# FlipDotModule.net
KiCad netlist of a schematic drawn in EAGLE
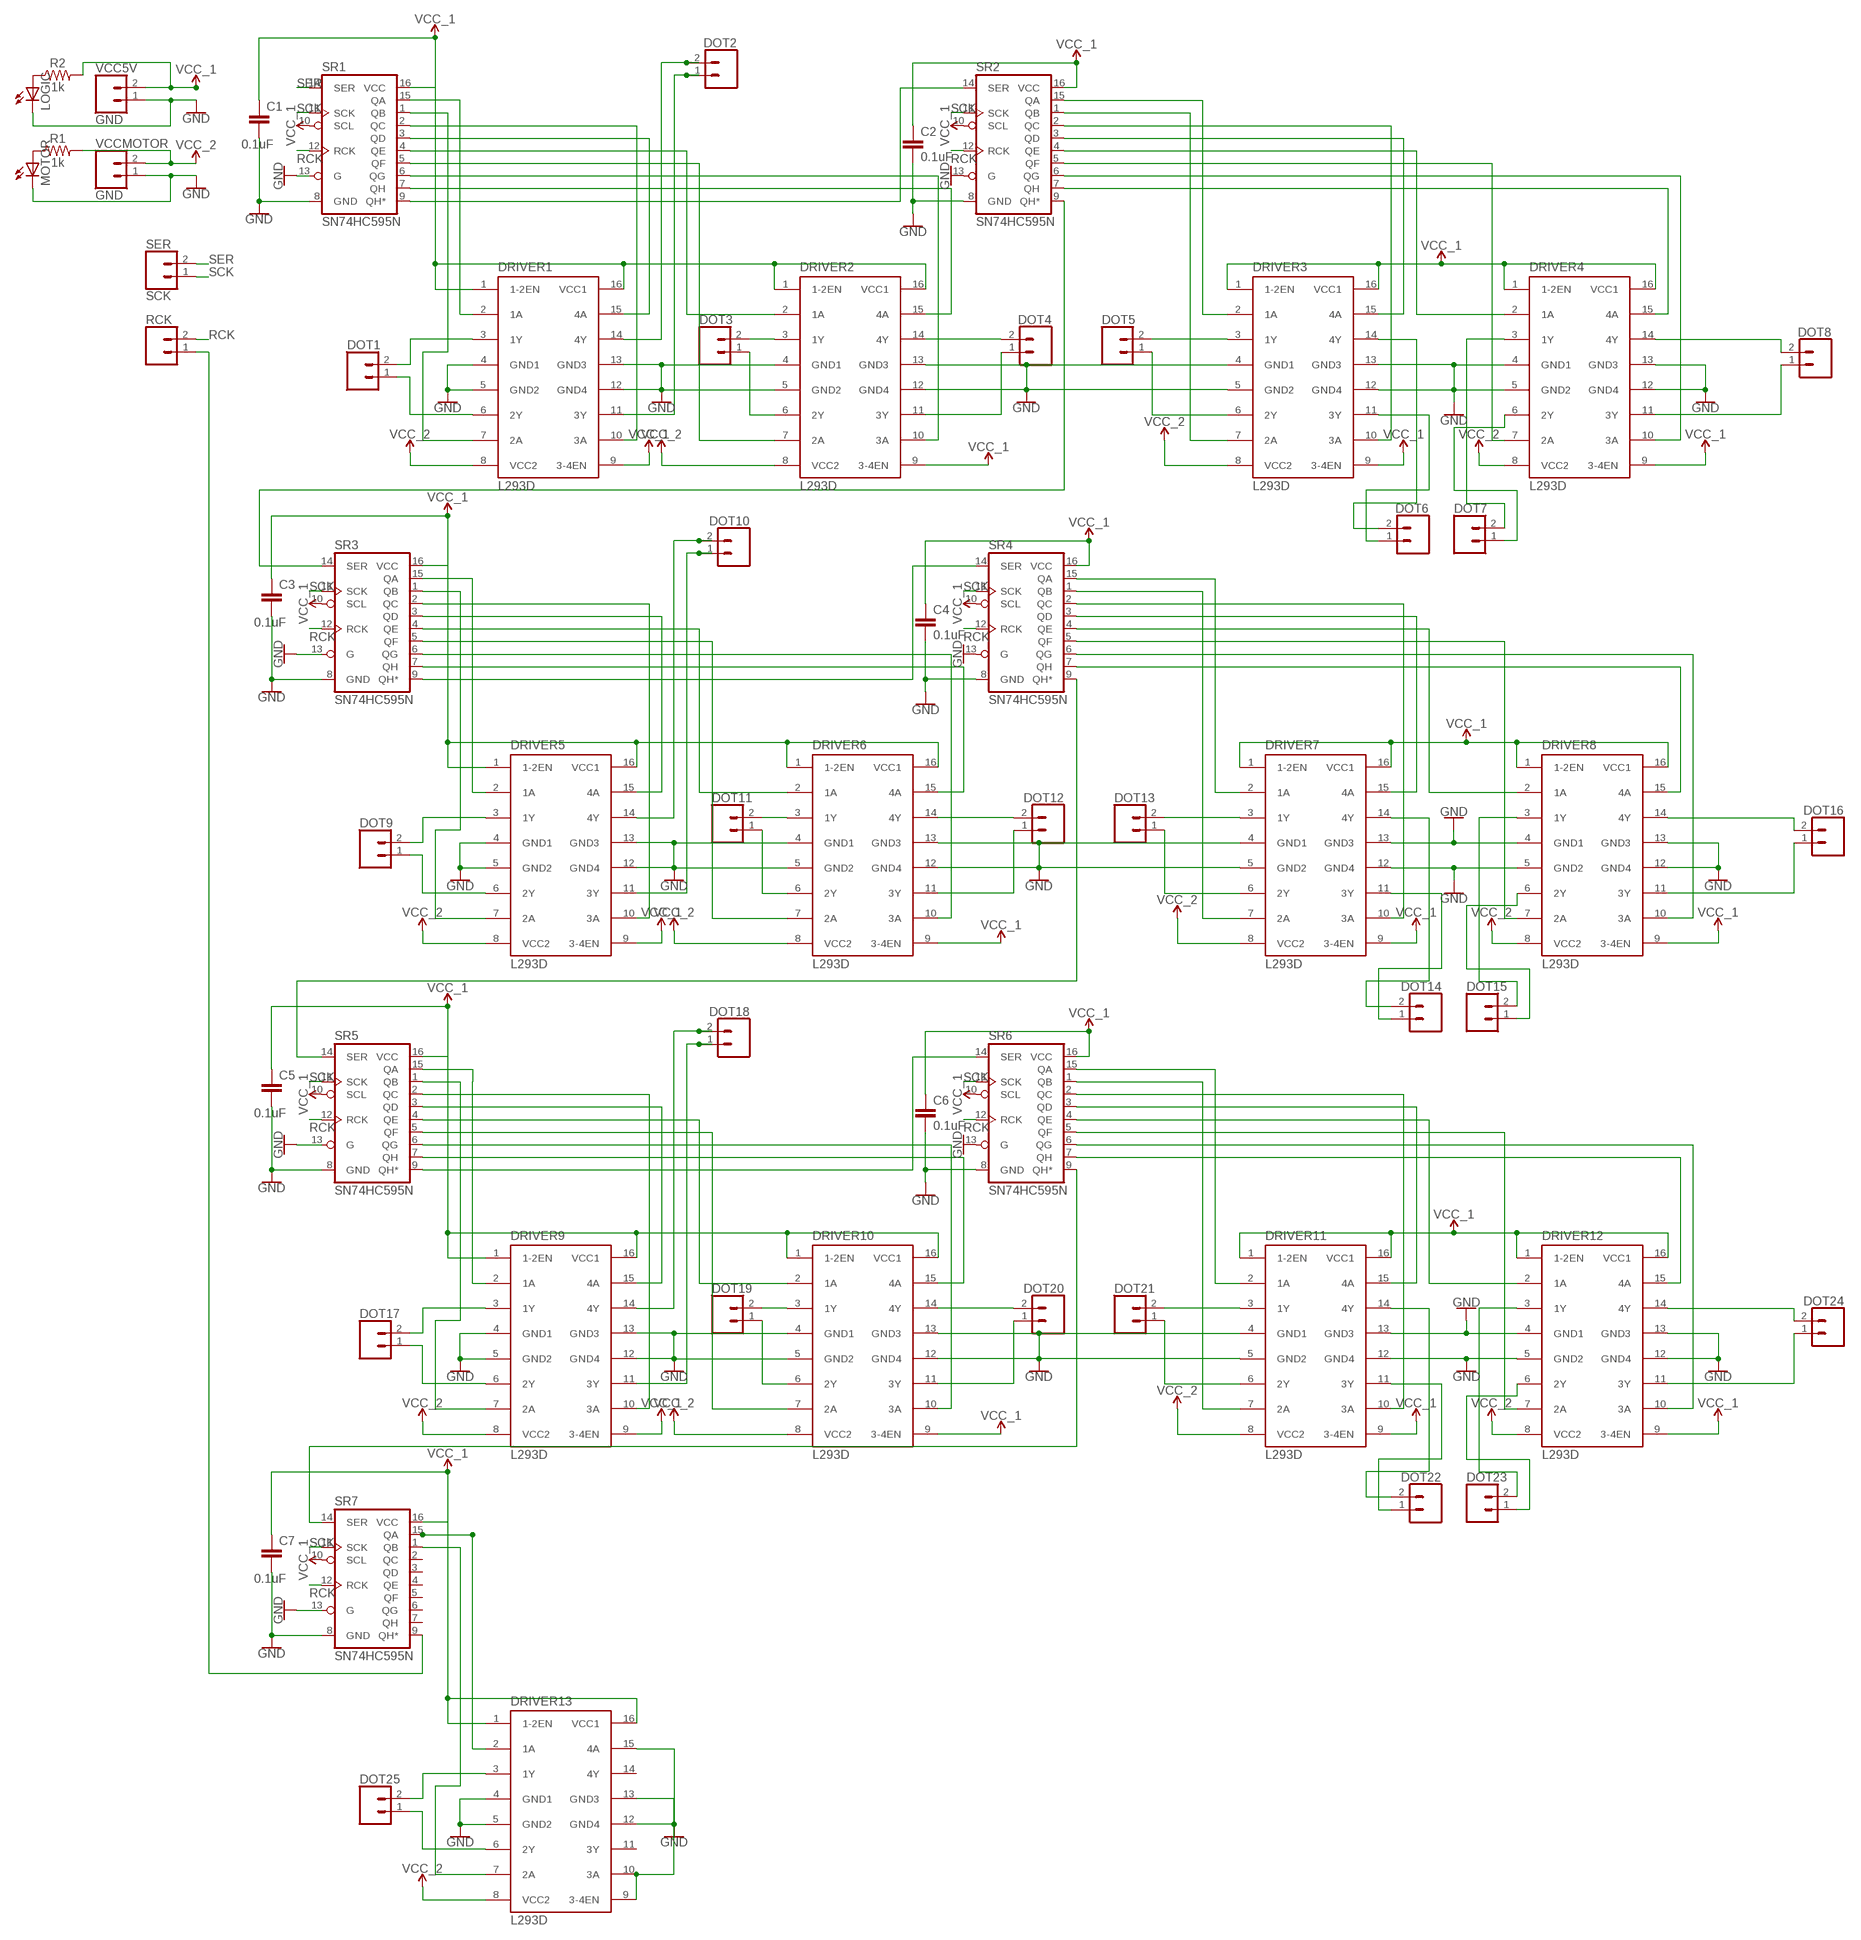
[diagram p0: schematic, sheet 1, part 1 of 2]
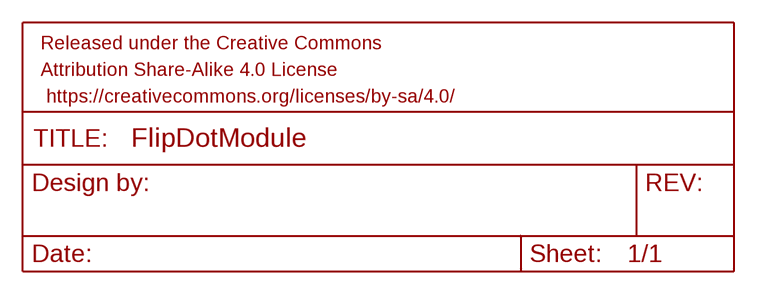
[diagram p1: schematic, sheet 1, part 2 of 2]

(export (version "E")
  (design (tool "Eeschema 10.0.6"))
  (components
    (comp (ref "C1")
      (value "0.1uF")
      (footprint "eagle-import:CAP-PTH-SMALL-KIT")
      (libsource (lib "eagle-import") (part "0.1UF-KIT-EZ-50V-20%"))
    )
    (comp (ref "C2")
      (value "0.1uF")
      (footprint "eagle-import:CAP-PTH-SMALL-KIT")
      (libsource (lib "eagle-import") (part "0.1UF-KIT-EZ-50V-20%"))
    )
    (comp (ref "C3")
      (value "0.1uF")
      (footprint "eagle-import:CAP-PTH-SMALL-KIT")
      (libsource (lib "eagle-import") (part "0.1UF-KIT-EZ-50V-20%"))
    )
    (comp (ref "C4")
      (value "0.1uF")
      (footprint "eagle-import:CAP-PTH-SMALL-KIT")
      (libsource (lib "eagle-import") (part "0.1UF-KIT-EZ-50V-20%"))
    )
    (comp (ref "C5")
      (value "0.1uF")
      (footprint "eagle-import:CAP-PTH-SMALL-KIT")
      (libsource (lib "eagle-import") (part "0.1UF-KIT-EZ-50V-20%"))
    )
    (comp (ref "C6")
      (value "0.1uF")
      (footprint "eagle-import:CAP-PTH-SMALL-KIT")
      (libsource (lib "eagle-import") (part "0.1UF-KIT-EZ-50V-20%"))
    )
    (comp (ref "C7")
      (value "0.1uF")
      (footprint "eagle-import:CAP-PTH-SMALL-KIT")
      (libsource (lib "eagle-import") (part "0.1UF-KIT-EZ-50V-20%"))
    )
    (comp (ref "DOT1")
      (value "CONN_025MM")
      (footprint "eagle-import:SCREWTERMINAL-5MM-2")
      (libsource (lib "eagle-import") (part "CONN_025MM"))
    )
    (comp (ref "DOT2")
      (value "CONN_025MM")
      (footprint "eagle-import:SCREWTERMINAL-5MM-2")
      (libsource (lib "eagle-import") (part "CONN_025MM"))
    )
    (comp (ref "DOT3")
      (value "CONN_025MM")
      (footprint "eagle-import:SCREWTERMINAL-5MM-2")
      (libsource (lib "eagle-import") (part "CONN_025MM"))
    )
    (comp (ref "DOT4")
      (value "CONN_025MM")
      (footprint "eagle-import:SCREWTERMINAL-5MM-2")
      (libsource (lib "eagle-import") (part "CONN_025MM"))
    )
    (comp (ref "DOT5")
      (value "CONN_025MM")
      (footprint "eagle-import:SCREWTERMINAL-5MM-2")
      (libsource (lib "eagle-import") (part "CONN_025MM"))
    )
    (comp (ref "DOT6")
      (value "CONN_025MM")
      (footprint "eagle-import:SCREWTERMINAL-5MM-2")
      (libsource (lib "eagle-import") (part "CONN_025MM"))
    )
    (comp (ref "DOT7")
      (value "CONN_025MM")
      (footprint "eagle-import:SCREWTERMINAL-5MM-2")
      (libsource (lib "eagle-import") (part "CONN_025MM"))
    )
    (comp (ref "DOT8")
      (value "CONN_025MM")
      (footprint "eagle-import:SCREWTERMINAL-5MM-2")
      (libsource (lib "eagle-import") (part "CONN_025MM"))
    )
    (comp (ref "DOT9")
      (value "CONN_025MM")
      (footprint "eagle-import:SCREWTERMINAL-5MM-2")
      (libsource (lib "eagle-import") (part "CONN_025MM"))
    )
    (comp (ref "DOT10")
      (value "CONN_025MM")
      (footprint "eagle-import:SCREWTERMINAL-5MM-2")
      (libsource (lib "eagle-import") (part "CONN_025MM"))
    )
    (comp (ref "DOT11")
      (value "CONN_025MM")
      (footprint "eagle-import:SCREWTERMINAL-5MM-2")
      (libsource (lib "eagle-import") (part "CONN_025MM"))
    )
    (comp (ref "DOT12")
      (value "CONN_025MM")
      (footprint "eagle-import:SCREWTERMINAL-5MM-2")
      (libsource (lib "eagle-import") (part "CONN_025MM"))
    )
    (comp (ref "DOT13")
      (value "CONN_025MM")
      (footprint "eagle-import:SCREWTERMINAL-5MM-2")
      (libsource (lib "eagle-import") (part "CONN_025MM"))
    )
    (comp (ref "DOT14")
      (value "CONN_025MM")
      (footprint "eagle-import:SCREWTERMINAL-5MM-2")
      (libsource (lib "eagle-import") (part "CONN_025MM"))
    )
    (comp (ref "DOT15")
      (value "CONN_025MM")
      (footprint "eagle-import:SCREWTERMINAL-5MM-2")
      (libsource (lib "eagle-import") (part "CONN_025MM"))
    )
    (comp (ref "DOT16")
      (value "CONN_025MM")
      (footprint "eagle-import:SCREWTERMINAL-5MM-2")
      (libsource (lib "eagle-import") (part "CONN_025MM"))
    )
    (comp (ref "DOT17")
      (value "CONN_025MM")
      (footprint "eagle-import:SCREWTERMINAL-5MM-2")
      (libsource (lib "eagle-import") (part "CONN_025MM"))
    )
    (comp (ref "DOT18")
      (value "CONN_025MM")
      (footprint "eagle-import:SCREWTERMINAL-5MM-2")
      (libsource (lib "eagle-import") (part "CONN_025MM"))
    )
    (comp (ref "DOT19")
      (value "CONN_025MM")
      (footprint "eagle-import:SCREWTERMINAL-5MM-2")
      (libsource (lib "eagle-import") (part "CONN_025MM"))
    )
    (comp (ref "DOT20")
      (value "CONN_025MM")
      (footprint "eagle-import:SCREWTERMINAL-5MM-2")
      (libsource (lib "eagle-import") (part "CONN_025MM"))
    )
    (comp (ref "DOT21")
      (value "CONN_025MM")
      (footprint "eagle-import:SCREWTERMINAL-5MM-2")
      (libsource (lib "eagle-import") (part "CONN_025MM"))
    )
    (comp (ref "DOT22")
      (value "CONN_025MM")
      (footprint "eagle-import:SCREWTERMINAL-5MM-2")
      (libsource (lib "eagle-import") (part "CONN_025MM"))
    )
    (comp (ref "DOT23")
      (value "CONN_025MM")
      (footprint "eagle-import:SCREWTERMINAL-5MM-2")
      (libsource (lib "eagle-import") (part "CONN_025MM"))
    )
    (comp (ref "DOT24")
      (value "CONN_025MM")
      (footprint "eagle-import:SCREWTERMINAL-5MM-2")
      (libsource (lib "eagle-import") (part "CONN_025MM"))
    )
    (comp (ref "DOT25")
      (value "CONN_025MM")
      (footprint "eagle-import:SCREWTERMINAL-5MM-2")
      (libsource (lib "eagle-import") (part "CONN_025MM"))
    )
    (comp (ref "DRIVER1")
      (value "L293D")
      (footprint "eagle-import:DIL16")
      (libsource (lib "eagle-import") (part "L293D"))
    )
    (comp (ref "DRIVER2")
      (value "L293D")
      (footprint "eagle-import:DIL16")
      (libsource (lib "eagle-import") (part "L293D"))
    )
    (comp (ref "DRIVER3")
      (value "L293D")
      (footprint "eagle-import:DIL16")
      (libsource (lib "eagle-import") (part "L293D"))
    )
    (comp (ref "DRIVER4")
      (value "L293D")
      (footprint "eagle-import:DIL16")
      (libsource (lib "eagle-import") (part "L293D"))
    )
    (comp (ref "DRIVER5")
      (value "L293D")
      (footprint "eagle-import:DIL16")
      (libsource (lib "eagle-import") (part "L293D"))
    )
    (comp (ref "DRIVER6")
      (value "L293D")
      (footprint "eagle-import:DIL16")
      (libsource (lib "eagle-import") (part "L293D"))
    )
    (comp (ref "DRIVER7")
      (value "L293D")
      (footprint "eagle-import:DIL16")
      (libsource (lib "eagle-import") (part "L293D"))
    )
    (comp (ref "DRIVER8")
      (value "L293D")
      (footprint "eagle-import:DIL16")
      (libsource (lib "eagle-import") (part "L293D"))
    )
    (comp (ref "DRIVER9")
      (value "L293D")
      (footprint "eagle-import:DIL16")
      (libsource (lib "eagle-import") (part "L293D"))
    )
    (comp (ref "DRIVER10")
      (value "L293D")
      (footprint "eagle-import:DIL16")
      (libsource (lib "eagle-import") (part "L293D"))
    )
    (comp (ref "DRIVER11")
      (value "L293D")
      (footprint "eagle-import:DIL16")
      (libsource (lib "eagle-import") (part "L293D"))
    )
    (comp (ref "DRIVER12")
      (value "L293D")
      (footprint "eagle-import:DIL16")
      (libsource (lib "eagle-import") (part "L293D"))
    )
    (comp (ref "DRIVER13")
      (value "L293D")
      (footprint "eagle-import:DIL16")
      (libsource (lib "eagle-import") (part "L293D"))
    )
    (comp (ref "FRAME1")
      (value "FRAME-LETTERNO_PACKAGE")
      (footprint "eagle-import:DUMMY")
      (fields (field (name "DESIGNER") "Nobody"))
      (libsource (lib "eagle-import") (part "FRAME-LETTERNO_PACKAGE"))
    )
    (comp (ref "LOGIC")
      (value "LED3MM")
      (footprint "eagle-import:LED3MM")
      (libsource (lib "eagle-import") (part "LED3MM"))
    )
    (comp (ref "MOTOR")
      (value "LED3MM")
      (footprint "eagle-import:LED3MM")
      (libsource (lib "eagle-import") (part "LED3MM"))
    )
    (comp (ref "R1")
      (value "1k")
      (footprint "eagle-import:AXIAL-0.3")
      (libsource (lib "eagle-import") (part "1KOHM-HORIZ-1/4W-5%"))
    )
    (comp (ref "R2")
      (value "1k")
      (footprint "eagle-import:AXIAL-0.3")
      (libsource (lib "eagle-import") (part "1KOHM-HORIZ-1/4W-5%"))
    )
    (comp (ref "RCK")
      (value "CONN_025MM")
      (footprint "eagle-import:SCREWTERMINAL-5MM-2")
      (libsource (lib "eagle-import") (part "CONN_025MM"))
    )
    (comp (ref "SER")
      (value "SCK")
      (footprint "eagle-import:SCREWTERMINAL-5MM-2")
      (libsource (lib "eagle-import") (part "CONN_025MM"))
    )
    (comp (ref "SR1")
      (value "SN74HC595N")
      (footprint "eagle-import:DIP16")
      (libsource (lib "eagle-import") (part "74595NHC"))
    )
    (comp (ref "SR2")
      (value "SN74HC595N")
      (footprint "eagle-import:DIP16")
      (libsource (lib "eagle-import") (part "74595NHC"))
    )
    (comp (ref "SR3")
      (value "SN74HC595N")
      (footprint "eagle-import:DIP16")
      (libsource (lib "eagle-import") (part "74595NHC"))
    )
    (comp (ref "SR4")
      (value "SN74HC595N")
      (footprint "eagle-import:DIP16")
      (libsource (lib "eagle-import") (part "74595NHC"))
    )
    (comp (ref "SR5")
      (value "SN74HC595N")
      (footprint "eagle-import:DIP16")
      (libsource (lib "eagle-import") (part "74595NHC"))
    )
    (comp (ref "SR6")
      (value "SN74HC595N")
      (footprint "eagle-import:DIP16")
      (libsource (lib "eagle-import") (part "74595NHC"))
    )
    (comp (ref "SR7")
      (value "SN74HC595N")
      (footprint "eagle-import:DIP16")
      (libsource (lib "eagle-import") (part "74595NHC"))
    )
    (comp (ref "VCC5V")
      (value "GND")
      (footprint "eagle-import:SCREWTERMINAL-5MM-2")
      (libsource (lib "eagle-import") (part "CONN_025MM"))
    )
    (comp (ref "VCCMOTOR")
      (value "GND")
      (footprint "eagle-import:SCREWTERMINAL-5MM-2")
      (libsource (lib "eagle-import") (part "CONN_025MM"))
    )
  )
  (nets
    (net (code "1") (name "/RCK") (class "Default")
      (node (ref "RCK") (pin "2") (pinfunction "2_2") (pintype "passive"))
      (node (ref "SR1") (pin "12") (pinfunction "RCK_12") (pintype "input"))
      (node (ref "SR2") (pin "12") (pinfunction "RCK_12") (pintype "input"))
      (node (ref "SR3") (pin "12") (pinfunction "RCK_12") (pintype "input"))
      (node (ref "SR4") (pin "12") (pinfunction "RCK_12") (pintype "input"))
      (node (ref "SR5") (pin "12") (pinfunction "RCK_12") (pintype "input"))
      (node (ref "SR6") (pin "12") (pinfunction "RCK_12") (pintype "input"))
      (node (ref "SR7") (pin "12") (pinfunction "RCK_12") (pintype "input"))
    )
    (net (code "2") (name "/SCK") (class "Default")
      (node (ref "SER") (pin "1") (pinfunction "1_1") (pintype "passive"))
      (node (ref "SR1") (pin "11") (pinfunction "SCK_11") (pintype "input"))
      (node (ref "SR2") (pin "11") (pinfunction "SCK_11") (pintype "input"))
      (node (ref "SR3") (pin "11") (pinfunction "SCK_11") (pintype "input"))
      (node (ref "SR4") (pin "11") (pinfunction "SCK_11") (pintype "input"))
      (node (ref "SR5") (pin "11") (pinfunction "SCK_11") (pintype "input"))
      (node (ref "SR6") (pin "11") (pinfunction "SCK_11") (pintype "input"))
      (node (ref "SR7") (pin "11") (pinfunction "SCK_11") (pintype "input"))
    )
    (net (code "3") (name "/SER") (class "Default")
      (node (ref "SER") (pin "2") (pinfunction "2_2") (pintype "passive"))
      (node (ref "SR1") (pin "14") (pinfunction "SER_14") (pintype "input"))
    )
    (net (code "4") (name "GND") (class "Default")
      (node (ref "C1") (pin "2") (pinfunction "2_2") (pintype "passive"))
      (node (ref "C2") (pin "2") (pinfunction "2_2") (pintype "passive"))
      (node (ref "C3") (pin "2") (pinfunction "2_2") (pintype "passive"))
      (node (ref "C4") (pin "2") (pinfunction "2_2") (pintype "passive"))
      (node (ref "C5") (pin "2") (pinfunction "2_2") (pintype "passive"))
      (node (ref "C6") (pin "2") (pinfunction "2_2") (pintype "passive"))
      (node (ref "C7") (pin "2") (pinfunction "2_2") (pintype "passive"))
      (node (ref "DRIVER1") (pin "12") (pinfunction "GND4_12") (pintype "power_in"))
      (node (ref "DRIVER1") (pin "13") (pinfunction "GND3_13") (pintype "power_in"))
      (node (ref "DRIVER1") (pin "4") (pinfunction "GND1_4") (pintype "power_in"))
      (node (ref "DRIVER1") (pin "5") (pinfunction "GND2_5") (pintype "power_in"))
      (node (ref "DRIVER10") (pin "12") (pinfunction "GND4_12") (pintype "power_in"))
      (node (ref "DRIVER10") (pin "13") (pinfunction "GND3_13") (pintype "power_in"))
      (node (ref "DRIVER10") (pin "4") (pinfunction "GND1_4") (pintype "power_in"))
      (node (ref "DRIVER10") (pin "5") (pinfunction "GND2_5") (pintype "power_in"))
      (node (ref "DRIVER11") (pin "12") (pinfunction "GND4_12") (pintype "power_in"))
      (node (ref "DRIVER11") (pin "13") (pinfunction "GND3_13") (pintype "power_in"))
      (node (ref "DRIVER11") (pin "4") (pinfunction "GND1_4") (pintype "power_in"))
      (node (ref "DRIVER11") (pin "5") (pinfunction "GND2_5") (pintype "power_in"))
      (node (ref "DRIVER12") (pin "12") (pinfunction "GND4_12") (pintype "power_in"))
      (node (ref "DRIVER12") (pin "13") (pinfunction "GND3_13") (pintype "power_in"))
      (node (ref "DRIVER12") (pin "4") (pinfunction "GND1_4") (pintype "power_in"))
      (node (ref "DRIVER12") (pin "5") (pinfunction "GND2_5") (pintype "power_in"))
      (node (ref "DRIVER13") (pin "10") (pinfunction "3A_10") (pintype "input"))
      (node (ref "DRIVER13") (pin "12") (pinfunction "GND4_12") (pintype "power_in"))
      (node (ref "DRIVER13") (pin "13") (pinfunction "GND3_13") (pintype "power_in"))
      (node (ref "DRIVER13") (pin "15") (pinfunction "4A_15") (pintype "input"))
      (node (ref "DRIVER13") (pin "4") (pinfunction "GND1_4") (pintype "power_in"))
      (node (ref "DRIVER13") (pin "5") (pinfunction "GND2_5") (pintype "power_in"))
      (node (ref "DRIVER13") (pin "9") (pinfunction "3-4EN_9") (pintype "input"))
      (node (ref "DRIVER2") (pin "12") (pinfunction "GND4_12") (pintype "power_in"))
      (node (ref "DRIVER2") (pin "13") (pinfunction "GND3_13") (pintype "power_in"))
      (node (ref "DRIVER2") (pin "4") (pinfunction "GND1_4") (pintype "power_in"))
      (node (ref "DRIVER2") (pin "5") (pinfunction "GND2_5") (pintype "power_in"))
      (node (ref "DRIVER3") (pin "12") (pinfunction "GND4_12") (pintype "power_in"))
      (node (ref "DRIVER3") (pin "13") (pinfunction "GND3_13") (pintype "power_in"))
      (node (ref "DRIVER3") (pin "4") (pinfunction "GND1_4") (pintype "power_in"))
      (node (ref "DRIVER3") (pin "5") (pinfunction "GND2_5") (pintype "power_in"))
      (node (ref "DRIVER4") (pin "12") (pinfunction "GND4_12") (pintype "power_in"))
      (node (ref "DRIVER4") (pin "13") (pinfunction "GND3_13") (pintype "power_in"))
      (node (ref "DRIVER4") (pin "4") (pinfunction "GND1_4") (pintype "power_in"))
      (node (ref "DRIVER4") (pin "5") (pinfunction "GND2_5") (pintype "power_in"))
      (node (ref "DRIVER5") (pin "12") (pinfunction "GND4_12") (pintype "power_in"))
      (node (ref "DRIVER5") (pin "13") (pinfunction "GND3_13") (pintype "power_in"))
      (node (ref "DRIVER5") (pin "4") (pinfunction "GND1_4") (pintype "power_in"))
      (node (ref "DRIVER5") (pin "5") (pinfunction "GND2_5") (pintype "power_in"))
      (node (ref "DRIVER6") (pin "12") (pinfunction "GND4_12") (pintype "power_in"))
      (node (ref "DRIVER6") (pin "13") (pinfunction "GND3_13") (pintype "power_in"))
      (node (ref "DRIVER6") (pin "4") (pinfunction "GND1_4") (pintype "power_in"))
      (node (ref "DRIVER6") (pin "5") (pinfunction "GND2_5") (pintype "power_in"))
      (node (ref "DRIVER7") (pin "12") (pinfunction "GND4_12") (pintype "power_in"))
      (node (ref "DRIVER7") (pin "13") (pinfunction "GND3_13") (pintype "power_in"))
      (node (ref "DRIVER7") (pin "4") (pinfunction "GND1_4") (pintype "power_in"))
      (node (ref "DRIVER7") (pin "5") (pinfunction "GND2_5") (pintype "power_in"))
      (node (ref "DRIVER8") (pin "12") (pinfunction "GND4_12") (pintype "power_in"))
      (node (ref "DRIVER8") (pin "13") (pinfunction "GND3_13") (pintype "power_in"))
      (node (ref "DRIVER8") (pin "4") (pinfunction "GND1_4") (pintype "power_in"))
      (node (ref "DRIVER8") (pin "5") (pinfunction "GND2_5") (pintype "power_in"))
      (node (ref "DRIVER9") (pin "12") (pinfunction "GND4_12") (pintype "power_in"))
      (node (ref "DRIVER9") (pin "13") (pinfunction "GND3_13") (pintype "power_in"))
      (node (ref "DRIVER9") (pin "4") (pinfunction "GND1_4") (pintype "power_in"))
      (node (ref "DRIVER9") (pin "5") (pinfunction "GND2_5") (pintype "power_in"))
      (node (ref "LOGIC") (pin "K") (pinfunction "C_K") (pintype "passive"))
      (node (ref "MOTOR") (pin "K") (pinfunction "C_K") (pintype "passive"))
      (node (ref "SR1") (pin "13") (pinfunction "G_13") (pintype "input"))
      (node (ref "SR1") (pin "8") (pinfunction "GND_8") (pintype "power_in"))
      (node (ref "SR2") (pin "13") (pinfunction "G_13") (pintype "input"))
      (node (ref "SR2") (pin "8") (pinfunction "GND_8") (pintype "power_in"))
      (node (ref "SR3") (pin "13") (pinfunction "G_13") (pintype "input"))
      (node (ref "SR3") (pin "8") (pinfunction "GND_8") (pintype "power_in"))
      (node (ref "SR4") (pin "13") (pinfunction "G_13") (pintype "input"))
      (node (ref "SR4") (pin "8") (pinfunction "GND_8") (pintype "power_in"))
      (node (ref "SR5") (pin "13") (pinfunction "G_13") (pintype "input"))
      (node (ref "SR5") (pin "8") (pinfunction "GND_8") (pintype "power_in"))
      (node (ref "SR6") (pin "13") (pinfunction "G_13") (pintype "input"))
      (node (ref "SR6") (pin "8") (pinfunction "GND_8") (pintype "power_in"))
      (node (ref "SR7") (pin "13") (pinfunction "G_13") (pintype "input"))
      (node (ref "SR7") (pin "8") (pinfunction "GND_8") (pintype "power_in"))
      (node (ref "VCC5V") (pin "1") (pinfunction "1_1") (pintype "passive"))
      (node (ref "VCCMOTOR") (pin "1") (pinfunction "1_1") (pintype "passive"))
    )
    (net (code "5") (name "Net-(DRIVER1-1A)") (class "Default")
      (node (ref "DRIVER1") (pin "2") (pinfunction "1A_2") (pintype "input"))
      (node (ref "SR1") (pin "15") (pinfunction "QA_15") (pintype "tri_state"))
    )
    (net (code "6") (name "Net-(DRIVER1-1Y)") (class "Default")
      (node (ref "DOT1") (pin "2") (pinfunction "2_2") (pintype "passive"))
      (node (ref "DRIVER1") (pin "3") (pinfunction "1Y_3") (pintype "output"))
    )
    (net (code "7") (name "Net-(DRIVER1-2A)") (class "Default")
      (node (ref "DRIVER1") (pin "7") (pinfunction "2A_7") (pintype "input"))
      (node (ref "SR1") (pin "1") (pinfunction "QB_1") (pintype "tri_state"))
    )
    (net (code "8") (name "Net-(DRIVER1-2Y)") (class "Default")
      (node (ref "DOT1") (pin "1") (pinfunction "1_1") (pintype "passive"))
      (node (ref "DRIVER1") (pin "6") (pinfunction "2Y_6") (pintype "output"))
    )
    (net (code "9") (name "Net-(DRIVER1-3A)") (class "Default")
      (node (ref "DRIVER1") (pin "10") (pinfunction "3A_10") (pintype "input"))
      (node (ref "SR1") (pin "2") (pinfunction "QC_2") (pintype "tri_state"))
    )
    (net (code "10") (name "Net-(DRIVER1-3Y)") (class "Default")
      (node (ref "DOT2") (pin "1") (pinfunction "1_1") (pintype "passive"))
      (node (ref "DRIVER1") (pin "11") (pinfunction "3Y_11") (pintype "output"))
    )
    (net (code "11") (name "Net-(DRIVER1-4A)") (class "Default")
      (node (ref "DRIVER1") (pin "15") (pinfunction "4A_15") (pintype "input"))
      (node (ref "SR1") (pin "3") (pinfunction "QD_3") (pintype "tri_state"))
    )
    (net (code "12") (name "Net-(DRIVER1-4Y)") (class "Default")
      (node (ref "DOT2") (pin "2") (pinfunction "2_2") (pintype "passive"))
      (node (ref "DRIVER1") (pin "14") (pinfunction "4Y_14") (pintype "output"))
    )
    (net (code "13") (name "Net-(DRIVER2-1A)") (class "Default")
      (node (ref "DRIVER2") (pin "2") (pinfunction "1A_2") (pintype "input"))
      (node (ref "SR1") (pin "4") (pinfunction "QE_4") (pintype "tri_state"))
    )
    (net (code "14") (name "Net-(DRIVER2-1Y)") (class "Default")
      (node (ref "DOT3") (pin "2") (pinfunction "2_2") (pintype "passive"))
      (node (ref "DRIVER2") (pin "3") (pinfunction "1Y_3") (pintype "output"))
    )
    (net (code "15") (name "Net-(DRIVER2-2A)") (class "Default")
      (node (ref "DRIVER2") (pin "7") (pinfunction "2A_7") (pintype "input"))
      (node (ref "SR1") (pin "5") (pinfunction "QF_5") (pintype "tri_state"))
    )
    (net (code "16") (name "Net-(DRIVER2-2Y)") (class "Default")
      (node (ref "DOT3") (pin "1") (pinfunction "1_1") (pintype "passive"))
      (node (ref "DRIVER2") (pin "6") (pinfunction "2Y_6") (pintype "output"))
    )
    (net (code "17") (name "Net-(DRIVER2-3A)") (class "Default")
      (node (ref "DRIVER2") (pin "10") (pinfunction "3A_10") (pintype "input"))
      (node (ref "SR1") (pin "6") (pinfunction "QG_6") (pintype "tri_state"))
    )
    (net (code "18") (name "Net-(DRIVER2-3Y)") (class "Default")
      (node (ref "DOT4") (pin "1") (pinfunction "1_1") (pintype "passive"))
      (node (ref "DRIVER2") (pin "11") (pinfunction "3Y_11") (pintype "output"))
    )
    (net (code "19") (name "Net-(DRIVER2-4A)") (class "Default")
      (node (ref "DRIVER2") (pin "15") (pinfunction "4A_15") (pintype "input"))
      (node (ref "SR1") (pin "7") (pinfunction "QH_7") (pintype "tri_state"))
    )
    (net (code "20") (name "Net-(DRIVER2-4Y)") (class "Default")
      (node (ref "DOT4") (pin "2") (pinfunction "2_2") (pintype "passive"))
      (node (ref "DRIVER2") (pin "14") (pinfunction "4Y_14") (pintype "output"))
    )
    (net (code "21") (name "Net-(DRIVER3-1A)") (class "Default")
      (node (ref "DRIVER3") (pin "2") (pinfunction "1A_2") (pintype "input"))
      (node (ref "SR2") (pin "15") (pinfunction "QA_15") (pintype "tri_state"))
    )
    (net (code "22") (name "Net-(DRIVER3-1Y)") (class "Default")
      (node (ref "DOT5") (pin "2") (pinfunction "2_2") (pintype "passive"))
      (node (ref "DRIVER3") (pin "3") (pinfunction "1Y_3") (pintype "output"))
    )
    (net (code "23") (name "Net-(DRIVER3-2A)") (class "Default")
      (node (ref "DRIVER3") (pin "7") (pinfunction "2A_7") (pintype "input"))
      (node (ref "SR2") (pin "1") (pinfunction "QB_1") (pintype "tri_state"))
    )
    (net (code "24") (name "Net-(DRIVER3-2Y)") (class "Default")
      (node (ref "DOT5") (pin "1") (pinfunction "1_1") (pintype "passive"))
      (node (ref "DRIVER3") (pin "6") (pinfunction "2Y_6") (pintype "output"))
    )
    (net (code "25") (name "Net-(DRIVER3-3A)") (class "Default")
      (node (ref "DRIVER3") (pin "10") (pinfunction "3A_10") (pintype "input"))
      (node (ref "SR2") (pin "2") (pinfunction "QC_2") (pintype "tri_state"))
    )
    (net (code "26") (name "Net-(DRIVER3-3Y)") (class "Default")
      (node (ref "DOT6") (pin "1") (pinfunction "1_1") (pintype "passive"))
      (node (ref "DRIVER3") (pin "11") (pinfunction "3Y_11") (pintype "output"))
    )
    (net (code "27") (name "Net-(DRIVER3-4A)") (class "Default")
      (node (ref "DRIVER3") (pin "15") (pinfunction "4A_15") (pintype "input"))
      (node (ref "SR2") (pin "3") (pinfunction "QD_3") (pintype "tri_state"))
    )
    (net (code "28") (name "Net-(DRIVER3-4Y)") (class "Default")
      (node (ref "DOT6") (pin "2") (pinfunction "2_2") (pintype "passive"))
      (node (ref "DRIVER3") (pin "14") (pinfunction "4Y_14") (pintype "output"))
    )
    (net (code "29") (name "Net-(DRIVER4-1A)") (class "Default")
      (node (ref "DRIVER4") (pin "2") (pinfunction "1A_2") (pintype "input"))
      (node (ref "SR2") (pin "4") (pinfunction "QE_4") (pintype "tri_state"))
    )
    (net (code "30") (name "Net-(DRIVER4-1Y)") (class "Default")
      (node (ref "DOT7") (pin "2") (pinfunction "2_2") (pintype "passive"))
      (node (ref "DRIVER4") (pin "3") (pinfunction "1Y_3") (pintype "output"))
    )
    (net (code "31") (name "Net-(DRIVER4-2A)") (class "Default")
      (node (ref "DRIVER4") (pin "7") (pinfunction "2A_7") (pintype "input"))
      (node (ref "SR2") (pin "5") (pinfunction "QF_5") (pintype "tri_state"))
    )
    (net (code "32") (name "Net-(DRIVER4-2Y)") (class "Default")
      (node (ref "DOT7") (pin "1") (pinfunction "1_1") (pintype "passive"))
      (node (ref "DRIVER4") (pin "6") (pinfunction "2Y_6") (pintype "output"))
    )
    (net (code "33") (name "Net-(DRIVER4-3A)") (class "Default")
      (node (ref "DRIVER4") (pin "10") (pinfunction "3A_10") (pintype "input"))
      (node (ref "SR2") (pin "6") (pinfunction "QG_6") (pintype "tri_state"))
    )
    (net (code "34") (name "Net-(DRIVER4-3Y)") (class "Default")
      (node (ref "DOT8") (pin "1") (pinfunction "1_1") (pintype "passive"))
      (node (ref "DRIVER4") (pin "11") (pinfunction "3Y_11") (pintype "output"))
    )
    (net (code "35") (name "Net-(DRIVER4-4A)") (class "Default")
      (node (ref "DRIVER4") (pin "15") (pinfunction "4A_15") (pintype "input"))
      (node (ref "SR2") (pin "7") (pinfunction "QH_7") (pintype "tri_state"))
    )
    (net (code "36") (name "Net-(DRIVER4-4Y)") (class "Default")
      (node (ref "DOT8") (pin "2") (pinfunction "2_2") (pintype "passive"))
      (node (ref "DRIVER4") (pin "14") (pinfunction "4Y_14") (pintype "output"))
    )
    (net (code "37") (name "Net-(DRIVER5-1A)") (class "Default")
      (node (ref "DRIVER5") (pin "2") (pinfunction "1A_2") (pintype "input"))
      (node (ref "SR3") (pin "15") (pinfunction "QA_15") (pintype "tri_state"))
    )
    (net (code "38") (name "Net-(DRIVER5-1Y)") (class "Default")
      (node (ref "DOT9") (pin "2") (pinfunction "2_2") (pintype "passive"))
      (node (ref "DRIVER5") (pin "3") (pinfunction "1Y_3") (pintype "output"))
    )
    (net (code "39") (name "Net-(DRIVER5-2A)") (class "Default")
      (node (ref "DRIVER5") (pin "7") (pinfunction "2A_7") (pintype "input"))
      (node (ref "SR3") (pin "1") (pinfunction "QB_1") (pintype "tri_state"))
    )
    (net (code "40") (name "Net-(DRIVER5-2Y)") (class "Default")
      (node (ref "DOT9") (pin "1") (pinfunction "1_1") (pintype "passive"))
      (node (ref "DRIVER5") (pin "6") (pinfunction "2Y_6") (pintype "output"))
    )
    (net (code "41") (name "Net-(DRIVER5-3A)") (class "Default")
      (node (ref "DRIVER5") (pin "10") (pinfunction "3A_10") (pintype "input"))
      (node (ref "SR3") (pin "2") (pinfunction "QC_2") (pintype "tri_state"))
    )
    (net (code "42") (name "Net-(DRIVER5-3Y)") (class "Default")
      (node (ref "DOT10") (pin "1") (pinfunction "1_1") (pintype "passive"))
      (node (ref "DRIVER5") (pin "11") (pinfunction "3Y_11") (pintype "output"))
    )
    (net (code "43") (name "Net-(DRIVER5-4A)") (class "Default")
      (node (ref "DRIVER5") (pin "15") (pinfunction "4A_15") (pintype "input"))
      (node (ref "SR3") (pin "3") (pinfunction "QD_3") (pintype "tri_state"))
    )
    (net (code "44") (name "Net-(DRIVER5-4Y)") (class "Default")
      (node (ref "DOT10") (pin "2") (pinfunction "2_2") (pintype "passive"))
      (node (ref "DRIVER5") (pin "14") (pinfunction "4Y_14") (pintype "output"))
    )
    (net (code "45") (name "Net-(DRIVER6-1A)") (class "Default")
      (node (ref "DRIVER6") (pin "2") (pinfunction "1A_2") (pintype "input"))
      (node (ref "SR3") (pin "4") (pinfunction "QE_4") (pintype "tri_state"))
    )
    (net (code "46") (name "Net-(DRIVER6-1Y)") (class "Default")
      (node (ref "DOT11") (pin "2") (pinfunction "2_2") (pintype "passive"))
      (node (ref "DRIVER6") (pin "3") (pinfunction "1Y_3") (pintype "output"))
    )
    (net (code "47") (name "Net-(DRIVER6-2A)") (class "Default")
      (node (ref "DRIVER6") (pin "7") (pinfunction "2A_7") (pintype "input"))
      (node (ref "SR3") (pin "5") (pinfunction "QF_5") (pintype "tri_state"))
    )
    (net (code "48") (name "Net-(DRIVER6-2Y)") (class "Default")
      (node (ref "DOT11") (pin "1") (pinfunction "1_1") (pintype "passive"))
      (node (ref "DRIVER6") (pin "6") (pinfunction "2Y_6") (pintype "output"))
    )
    (net (code "49") (name "Net-(DRIVER6-3A)") (class "Default")
      (node (ref "DRIVER6") (pin "10") (pinfunction "3A_10") (pintype "input"))
      (node (ref "SR3") (pin "6") (pinfunction "QG_6") (pintype "tri_state"))
    )
    (net (code "50") (name "Net-(DRIVER6-3Y)") (class "Default")
      (node (ref "DOT12") (pin "1") (pinfunction "1_1") (pintype "passive"))
      (node (ref "DRIVER6") (pin "11") (pinfunction "3Y_11") (pintype "output"))
    )
    (net (code "51") (name "Net-(DRIVER6-4A)") (class "Default")
      (node (ref "DRIVER6") (pin "15") (pinfunction "4A_15") (pintype "input"))
      (node (ref "SR3") (pin "7") (pinfunction "QH_7") (pintype "tri_state"))
    )
    (net (code "52") (name "Net-(DRIVER6-4Y)") (class "Default")
      (node (ref "DOT12") (pin "2") (pinfunction "2_2") (pintype "passive"))
      (node (ref "DRIVER6") (pin "14") (pinfunction "4Y_14") (pintype "output"))
    )
    (net (code "53") (name "Net-(DRIVER7-1A)") (class "Default")
      (node (ref "DRIVER7") (pin "2") (pinfunction "1A_2") (pintype "input"))
      (node (ref "SR4") (pin "15") (pinfunction "QA_15") (pintype "tri_state"))
    )
    (net (code "54") (name "Net-(DRIVER7-1Y)") (class "Default")
      (node (ref "DOT13") (pin "2") (pinfunction "2_2") (pintype "passive"))
      (node (ref "DRIVER7") (pin "3") (pinfunction "1Y_3") (pintype "output"))
    )
    (net (code "55") (name "Net-(DRIVER7-2A)") (class "Default")
      (node (ref "DRIVER7") (pin "7") (pinfunction "2A_7") (pintype "input"))
      (node (ref "SR4") (pin "1") (pinfunction "QB_1") (pintype "tri_state"))
    )
    (net (code "56") (name "Net-(DRIVER7-2Y)") (class "Default")
      (node (ref "DOT13") (pin "1") (pinfunction "1_1") (pintype "passive"))
      (node (ref "DRIVER7") (pin "6") (pinfunction "2Y_6") (pintype "output"))
    )
    (net (code "57") (name "Net-(DRIVER7-3A)") (class "Default")
      (node (ref "DRIVER7") (pin "10") (pinfunction "3A_10") (pintype "input"))
      (node (ref "SR4") (pin "2") (pinfunction "QC_2") (pintype "tri_state"))
    )
    (net (code "58") (name "Net-(DRIVER7-3Y)") (class "Default")
      (node (ref "DOT14") (pin "1") (pinfunction "1_1") (pintype "passive"))
      (node (ref "DRIVER7") (pin "11") (pinfunction "3Y_11") (pintype "output"))
    )
    (net (code "59") (name "Net-(DRIVER7-4A)") (class "Default")
      (node (ref "DRIVER7") (pin "15") (pinfunction "4A_15") (pintype "input"))
      (node (ref "SR4") (pin "3") (pinfunction "QD_3") (pintype "tri_state"))
    )
    (net (code "60") (name "Net-(DRIVER7-4Y)") (class "Default")
      (node (ref "DOT14") (pin "2") (pinfunction "2_2") (pintype "passive"))
      (node (ref "DRIVER7") (pin "14") (pinfunction "4Y_14") (pintype "output"))
    )
    (net (code "61") (name "Net-(DRIVER8-1A)") (class "Default")
      (node (ref "DRIVER8") (pin "2") (pinfunction "1A_2") (pintype "input"))
      (node (ref "SR4") (pin "4") (pinfunction "QE_4") (pintype "tri_state"))
    )
    (net (code "62") (name "Net-(DRIVER8-1Y)") (class "Default")
      (node (ref "DOT15") (pin "2") (pinfunction "2_2") (pintype "passive"))
      (node (ref "DRIVER8") (pin "3") (pinfunction "1Y_3") (pintype "output"))
    )
    (net (code "63") (name "Net-(DRIVER8-2A)") (class "Default")
      (node (ref "DRIVER8") (pin "7") (pinfunction "2A_7") (pintype "input"))
      (node (ref "SR4") (pin "5") (pinfunction "QF_5") (pintype "tri_state"))
    )
    (net (code "64") (name "Net-(DRIVER8-2Y)") (class "Default")
      (node (ref "DOT15") (pin "1") (pinfunction "1_1") (pintype "passive"))
      (node (ref "DRIVER8") (pin "6") (pinfunction "2Y_6") (pintype "output"))
    )
    (net (code "65") (name "Net-(DRIVER8-3A)") (class "Default")
      (node (ref "DRIVER8") (pin "10") (pinfunction "3A_10") (pintype "input"))
      (node (ref "SR4") (pin "6") (pinfunction "QG_6") (pintype "tri_state"))
    )
    (net (code "66") (name "Net-(DRIVER8-3Y)") (class "Default")
      (node (ref "DOT16") (pin "1") (pinfunction "1_1") (pintype "passive"))
      (node (ref "DRIVER8") (pin "11") (pinfunction "3Y_11") (pintype "output"))
    )
    (net (code "67") (name "Net-(DRIVER8-4A)") (class "Default")
      (node (ref "DRIVER8") (pin "15") (pinfunction "4A_15") (pintype "input"))
      (node (ref "SR4") (pin "7") (pinfunction "QH_7") (pintype "tri_state"))
    )
    (net (code "68") (name "Net-(DRIVER8-4Y)") (class "Default")
      (node (ref "DOT16") (pin "2") (pinfunction "2_2") (pintype "passive"))
      (node (ref "DRIVER8") (pin "14") (pinfunction "4Y_14") (pintype "output"))
    )
    (net (code "69") (name "Net-(DRIVER9-1A)") (class "Default")
      (node (ref "DRIVER9") (pin "2") (pinfunction "1A_2") (pintype "input"))
      (node (ref "SR5") (pin "15") (pinfunction "QA_15") (pintype "tri_state"))
    )
    (net (code "70") (name "Net-(DRIVER9-1Y)") (class "Default")
      (node (ref "DOT17") (pin "2") (pinfunction "2_2") (pintype "passive"))
      (node (ref "DRIVER9") (pin "3") (pinfunction "1Y_3") (pintype "output"))
    )
    (net (code "71") (name "Net-(DRIVER9-2A)") (class "Default")
      (node (ref "DRIVER9") (pin "7") (pinfunction "2A_7") (pintype "input"))
      (node (ref "SR5") (pin "1") (pinfunction "QB_1") (pintype "tri_state"))
    )
    (net (code "72") (name "Net-(DRIVER9-2Y)") (class "Default")
      (node (ref "DOT17") (pin "1") (pinfunction "1_1") (pintype "passive"))
      (node (ref "DRIVER9") (pin "6") (pinfunction "2Y_6") (pintype "output"))
    )
    (net (code "73") (name "Net-(DRIVER9-3A)") (class "Default")
      (node (ref "DRIVER9") (pin "10") (pinfunction "3A_10") (pintype "input"))
      (node (ref "SR5") (pin "2") (pinfunction "QC_2") (pintype "tri_state"))
    )
    (net (code "74") (name "Net-(DRIVER9-3Y)") (class "Default")
      (node (ref "DOT18") (pin "1") (pinfunction "1_1") (pintype "passive"))
      (node (ref "DRIVER9") (pin "11") (pinfunction "3Y_11") (pintype "output"))
    )
    (net (code "75") (name "Net-(DRIVER9-4A)") (class "Default")
      (node (ref "DRIVER9") (pin "15") (pinfunction "4A_15") (pintype "input"))
      (node (ref "SR5") (pin "3") (pinfunction "QD_3") (pintype "tri_state"))
    )
    (net (code "76") (name "Net-(DRIVER9-4Y)") (class "Default")
      (node (ref "DOT18") (pin "2") (pinfunction "2_2") (pintype "passive"))
      (node (ref "DRIVER9") (pin "14") (pinfunction "4Y_14") (pintype "output"))
    )
    (net (code "77") (name "Net-(DRIVER10-1A)") (class "Default")
      (node (ref "DRIVER10") (pin "2") (pinfunction "1A_2") (pintype "input"))
      (node (ref "SR5") (pin "4") (pinfunction "QE_4") (pintype "tri_state"))
    )
    (net (code "78") (name "Net-(DRIVER10-1Y)") (class "Default")
      (node (ref "DOT19") (pin "2") (pinfunction "2_2") (pintype "passive"))
      (node (ref "DRIVER10") (pin "3") (pinfunction "1Y_3") (pintype "output"))
    )
    (net (code "79") (name "Net-(DRIVER10-2A)") (class "Default")
      (node (ref "DRIVER10") (pin "7") (pinfunction "2A_7") (pintype "input"))
      (node (ref "SR5") (pin "5") (pinfunction "QF_5") (pintype "tri_state"))
    )
    (net (code "80") (name "Net-(DRIVER10-2Y)") (class "Default")
      (node (ref "DOT19") (pin "1") (pinfunction "1_1") (pintype "passive"))
      (node (ref "DRIVER10") (pin "6") (pinfunction "2Y_6") (pintype "output"))
    )
    (net (code "81") (name "Net-(DRIVER10-3A)") (class "Default")
      (node (ref "DRIVER10") (pin "10") (pinfunction "3A_10") (pintype "input"))
      (node (ref "SR5") (pin "6") (pinfunction "QG_6") (pintype "tri_state"))
    )
    (net (code "82") (name "Net-(DRIVER10-3Y)") (class "Default")
      (node (ref "DOT20") (pin "1") (pinfunction "1_1") (pintype "passive"))
      (node (ref "DRIVER10") (pin "11") (pinfunction "3Y_11") (pintype "output"))
    )
    (net (code "83") (name "Net-(DRIVER10-4A)") (class "Default")
      (node (ref "DRIVER10") (pin "15") (pinfunction "4A_15") (pintype "input"))
      (node (ref "SR5") (pin "7") (pinfunction "QH_7") (pintype "tri_state"))
    )
    (net (code "84") (name "Net-(DRIVER10-4Y)") (class "Default")
      (node (ref "DOT20") (pin "2") (pinfunction "2_2") (pintype "passive"))
      (node (ref "DRIVER10") (pin "14") (pinfunction "4Y_14") (pintype "output"))
    )
    (net (code "85") (name "Net-(DRIVER11-1A)") (class "Default")
      (node (ref "DRIVER11") (pin "2") (pinfunction "1A_2") (pintype "input"))
      (node (ref "SR6") (pin "15") (pinfunction "QA_15") (pintype "tri_state"))
    )
    (net (code "86") (name "Net-(DRIVER11-1Y)") (class "Default")
      (node (ref "DOT21") (pin "2") (pinfunction "2_2") (pintype "passive"))
      (node (ref "DRIVER11") (pin "3") (pinfunction "1Y_3") (pintype "output"))
    )
    (net (code "87") (name "Net-(DRIVER11-2A)") (class "Default")
      (node (ref "DRIVER11") (pin "7") (pinfunction "2A_7") (pintype "input"))
      (node (ref "SR6") (pin "1") (pinfunction "QB_1") (pintype "tri_state"))
    )
    (net (code "88") (name "Net-(DRIVER11-2Y)") (class "Default")
      (node (ref "DOT21") (pin "1") (pinfunction "1_1") (pintype "passive"))
      (node (ref "DRIVER11") (pin "6") (pinfunction "2Y_6") (pintype "output"))
    )
    (net (code "89") (name "Net-(DRIVER11-3A)") (class "Default")
      (node (ref "DRIVER11") (pin "10") (pinfunction "3A_10") (pintype "input"))
      (node (ref "SR6") (pin "2") (pinfunction "QC_2") (pintype "tri_state"))
    )
    (net (code "90") (name "Net-(DRIVER11-3Y)") (class "Default")
      (node (ref "DOT22") (pin "1") (pinfunction "1_1") (pintype "passive"))
      (node (ref "DRIVER11") (pin "11") (pinfunction "3Y_11") (pintype "output"))
    )
    (net (code "91") (name "Net-(DRIVER11-4A)") (class "Default")
      (node (ref "DRIVER11") (pin "15") (pinfunction "4A_15") (pintype "input"))
      (node (ref "SR6") (pin "3") (pinfunction "QD_3") (pintype "tri_state"))
    )
    (net (code "92") (name "Net-(DRIVER11-4Y)") (class "Default")
      (node (ref "DOT22") (pin "2") (pinfunction "2_2") (pintype "passive"))
      (node (ref "DRIVER11") (pin "14") (pinfunction "4Y_14") (pintype "output"))
    )
    (net (code "93") (name "Net-(DRIVER12-1A)") (class "Default")
      (node (ref "DRIVER12") (pin "2") (pinfunction "1A_2") (pintype "input"))
      (node (ref "SR6") (pin "4") (pinfunction "QE_4") (pintype "tri_state"))
    )
    (net (code "94") (name "Net-(DRIVER12-1Y)") (class "Default")
      (node (ref "DOT23") (pin "2") (pinfunction "2_2") (pintype "passive"))
      (node (ref "DRIVER12") (pin "3") (pinfunction "1Y_3") (pintype "output"))
    )
    (net (code "95") (name "Net-(DRIVER12-2A)") (class "Default")
      (node (ref "DRIVER12") (pin "7") (pinfunction "2A_7") (pintype "input"))
      (node (ref "SR6") (pin "5") (pinfunction "QF_5") (pintype "tri_state"))
    )
    (net (code "96") (name "Net-(DRIVER12-2Y)") (class "Default")
      (node (ref "DOT23") (pin "1") (pinfunction "1_1") (pintype "passive"))
      (node (ref "DRIVER12") (pin "6") (pinfunction "2Y_6") (pintype "output"))
    )
    (net (code "97") (name "Net-(DRIVER12-3A)") (class "Default")
      (node (ref "DRIVER12") (pin "10") (pinfunction "3A_10") (pintype "input"))
      (node (ref "SR6") (pin "6") (pinfunction "QG_6") (pintype "tri_state"))
    )
    (net (code "98") (name "Net-(DRIVER12-3Y)") (class "Default")
      (node (ref "DOT24") (pin "1") (pinfunction "1_1") (pintype "passive"))
      (node (ref "DRIVER12") (pin "11") (pinfunction "3Y_11") (pintype "output"))
    )
    (net (code "99") (name "Net-(DRIVER12-4A)") (class "Default")
      (node (ref "DRIVER12") (pin "15") (pinfunction "4A_15") (pintype "input"))
      (node (ref "SR6") (pin "7") (pinfunction "QH_7") (pintype "tri_state"))
    )
    (net (code "100") (name "Net-(DRIVER12-4Y)") (class "Default")
      (node (ref "DOT24") (pin "2") (pinfunction "2_2") (pintype "passive"))
      (node (ref "DRIVER12") (pin "14") (pinfunction "4Y_14") (pintype "output"))
    )
    (net (code "101") (name "Net-(DRIVER13-1A)") (class "Default")
      (node (ref "DRIVER13") (pin "2") (pinfunction "1A_2") (pintype "input"))
      (node (ref "SR7") (pin "15") (pinfunction "QA_15") (pintype "tri_state"))
    )
    (net (code "102") (name "Net-(DRIVER13-1Y)") (class "Default")
      (node (ref "DOT25") (pin "2") (pinfunction "2_2") (pintype "passive"))
      (node (ref "DRIVER13") (pin "3") (pinfunction "1Y_3") (pintype "output"))
    )
    (net (code "103") (name "Net-(DRIVER13-2A)") (class "Default")
      (node (ref "DRIVER13") (pin "7") (pinfunction "2A_7") (pintype "input"))
      (node (ref "SR7") (pin "1") (pinfunction "QB_1") (pintype "tri_state"))
    )
    (net (code "104") (name "Net-(DRIVER13-2Y)") (class "Default")
      (node (ref "DOT25") (pin "1") (pinfunction "1_1") (pintype "passive"))
      (node (ref "DRIVER13") (pin "6") (pinfunction "2Y_6") (pintype "output"))
    )
    (net (code "105") (name "Net-(R1-1)") (class "Default")
      (node (ref "MOTOR") (pin "A") (pinfunction "A_A") (pintype "passive"))
      (node (ref "R1") (pin "P$1") (pinfunction "1_P$1") (pintype "passive"))
    )
    (net (code "106") (name "Net-(R2-1)") (class "Default")
      (node (ref "LOGIC") (pin "A") (pinfunction "A_A") (pintype "passive"))
      (node (ref "R2") (pin "P$1") (pinfunction "1_P$1") (pintype "passive"))
    )
    (net (code "107") (name "Net-(SR1-QH*)") (class "Default")
      (node (ref "SR1") (pin "9") (pinfunction "QH*_9") (pintype "tri_state"))
      (node (ref "SR2") (pin "14") (pinfunction "SER_14") (pintype "input"))
    )
    (net (code "108") (name "Net-(SR2-QH*)") (class "Default")
      (node (ref "SR2") (pin "9") (pinfunction "QH*_9") (pintype "tri_state"))
      (node (ref "SR3") (pin "14") (pinfunction "SER_14") (pintype "input"))
    )
    (net (code "109") (name "Net-(SR3-QH*)") (class "Default")
      (node (ref "SR3") (pin "9") (pinfunction "QH*_9") (pintype "tri_state"))
      (node (ref "SR4") (pin "14") (pinfunction "SER_14") (pintype "input"))
    )
    (net (code "110") (name "Net-(SR4-QH*)") (class "Default")
      (node (ref "SR4") (pin "9") (pinfunction "QH*_9") (pintype "tri_state"))
      (node (ref "SR5") (pin "14") (pinfunction "SER_14") (pintype "input"))
    )
    (net (code "111") (name "Net-(SR5-QH*)") (class "Default")
      (node (ref "SR5") (pin "9") (pinfunction "QH*_9") (pintype "tri_state"))
      (node (ref "SR6") (pin "14") (pinfunction "SER_14") (pintype "input"))
    )
    (net (code "112") (name "Net-(SR6-QH*)") (class "Default")
      (node (ref "SR6") (pin "9") (pinfunction "QH*_9") (pintype "tri_state"))
      (node (ref "SR7") (pin "14") (pinfunction "SER_14") (pintype "input"))
    )
    (net (code "113") (name "Net-(SR7-QH*)") (class "Default")
      (node (ref "RCK") (pin "1") (pinfunction "1_1") (pintype "passive"))
      (node (ref "SR7") (pin "9") (pinfunction "QH*_9") (pintype "tri_state"))
    )
    (net (code "114") (name "VCC_1") (class "Default")
      (node (ref "C1") (pin "1") (pinfunction "1_1") (pintype "passive"))
      (node (ref "C2") (pin "1") (pinfunction "1_1") (pintype "passive"))
      (node (ref "C3") (pin "1") (pinfunction "1_1") (pintype "passive"))
      (node (ref "C4") (pin "1") (pinfunction "1_1") (pintype "passive"))
      (node (ref "C5") (pin "1") (pinfunction "1_1") (pintype "passive"))
      (node (ref "C6") (pin "1") (pinfunction "1_1") (pintype "passive"))
      (node (ref "C7") (pin "1") (pinfunction "1_1") (pintype "passive"))
      (node (ref "DRIVER1") (pin "1") (pinfunction "1-2EN_1") (pintype "input"))
      (node (ref "DRIVER1") (pin "16") (pinfunction "VCC1_16") (pintype "power_in"))
      (node (ref "DRIVER1") (pin "9") (pinfunction "3-4EN_9") (pintype "input"))
      (node (ref "DRIVER10") (pin "1") (pinfunction "1-2EN_1") (pintype "input"))
      (node (ref "DRIVER10") (pin "16") (pinfunction "VCC1_16") (pintype "power_in"))
      (node (ref "DRIVER10") (pin "9") (pinfunction "3-4EN_9") (pintype "input"))
      (node (ref "DRIVER11") (pin "1") (pinfunction "1-2EN_1") (pintype "input"))
      (node (ref "DRIVER11") (pin "16") (pinfunction "VCC1_16") (pintype "power_in"))
      (node (ref "DRIVER11") (pin "9") (pinfunction "3-4EN_9") (pintype "input"))
      (node (ref "DRIVER12") (pin "1") (pinfunction "1-2EN_1") (pintype "input"))
      (node (ref "DRIVER12") (pin "16") (pinfunction "VCC1_16") (pintype "power_in"))
      (node (ref "DRIVER12") (pin "9") (pinfunction "3-4EN_9") (pintype "input"))
      (node (ref "DRIVER13") (pin "1") (pinfunction "1-2EN_1") (pintype "input"))
      (node (ref "DRIVER13") (pin "16") (pinfunction "VCC1_16") (pintype "power_in"))
      (node (ref "DRIVER2") (pin "1") (pinfunction "1-2EN_1") (pintype "input"))
      (node (ref "DRIVER2") (pin "16") (pinfunction "VCC1_16") (pintype "power_in"))
      (node (ref "DRIVER2") (pin "9") (pinfunction "3-4EN_9") (pintype "input"))
      (node (ref "DRIVER3") (pin "1") (pinfunction "1-2EN_1") (pintype "input"))
      (node (ref "DRIVER3") (pin "16") (pinfunction "VCC1_16") (pintype "power_in"))
      (node (ref "DRIVER3") (pin "9") (pinfunction "3-4EN_9") (pintype "input"))
      (node (ref "DRIVER4") (pin "1") (pinfunction "1-2EN_1") (pintype "input"))
      (node (ref "DRIVER4") (pin "16") (pinfunction "VCC1_16") (pintype "power_in"))
      (node (ref "DRIVER4") (pin "9") (pinfunction "3-4EN_9") (pintype "input"))
      (node (ref "DRIVER5") (pin "1") (pinfunction "1-2EN_1") (pintype "input"))
      (node (ref "DRIVER5") (pin "16") (pinfunction "VCC1_16") (pintype "power_in"))
      (node (ref "DRIVER5") (pin "9") (pinfunction "3-4EN_9") (pintype "input"))
      (node (ref "DRIVER6") (pin "1") (pinfunction "1-2EN_1") (pintype "input"))
      (node (ref "DRIVER6") (pin "16") (pinfunction "VCC1_16") (pintype "power_in"))
      (node (ref "DRIVER6") (pin "9") (pinfunction "3-4EN_9") (pintype "input"))
      (node (ref "DRIVER7") (pin "1") (pinfunction "1-2EN_1") (pintype "input"))
      (node (ref "DRIVER7") (pin "16") (pinfunction "VCC1_16") (pintype "power_in"))
      (node (ref "DRIVER7") (pin "9") (pinfunction "3-4EN_9") (pintype "input"))
      (node (ref "DRIVER8") (pin "1") (pinfunction "1-2EN_1") (pintype "input"))
      (node (ref "DRIVER8") (pin "16") (pinfunction "VCC1_16") (pintype "power_in"))
      (node (ref "DRIVER8") (pin "9") (pinfunction "3-4EN_9") (pintype "input"))
      (node (ref "DRIVER9") (pin "1") (pinfunction "1-2EN_1") (pintype "input"))
      (node (ref "DRIVER9") (pin "16") (pinfunction "VCC1_16") (pintype "power_in"))
      (node (ref "DRIVER9") (pin "9") (pinfunction "3-4EN_9") (pintype "input"))
      (node (ref "R2") (pin "P$2") (pinfunction "2_P$2") (pintype "passive"))
      (node (ref "SR1") (pin "10") (pinfunction "SCL_10") (pintype "input"))
      (node (ref "SR1") (pin "16") (pinfunction "VCC_16") (pintype "power_in"))
      (node (ref "SR2") (pin "10") (pinfunction "SCL_10") (pintype "input"))
      (node (ref "SR2") (pin "16") (pinfunction "VCC_16") (pintype "power_in"))
      (node (ref "SR3") (pin "10") (pinfunction "SCL_10") (pintype "input"))
      (node (ref "SR3") (pin "16") (pinfunction "VCC_16") (pintype "power_in"))
      (node (ref "SR4") (pin "10") (pinfunction "SCL_10") (pintype "input"))
      (node (ref "SR4") (pin "16") (pinfunction "VCC_16") (pintype "power_in"))
      (node (ref "SR5") (pin "10") (pinfunction "SCL_10") (pintype "input"))
      (node (ref "SR5") (pin "16") (pinfunction "VCC_16") (pintype "power_in"))
      (node (ref "SR6") (pin "10") (pinfunction "SCL_10") (pintype "input"))
      (node (ref "SR6") (pin "16") (pinfunction "VCC_16") (pintype "power_in"))
      (node (ref "SR7") (pin "10") (pinfunction "SCL_10") (pintype "input"))
      (node (ref "SR7") (pin "16") (pinfunction "VCC_16") (pintype "power_in"))
      (node (ref "VCC5V") (pin "2") (pinfunction "2_2") (pintype "passive"))
    )
    (net (code "115") (name "VCC_2") (class "Default")
      (node (ref "DRIVER1") (pin "8") (pinfunction "VCC2_8") (pintype "power_in"))
      (node (ref "DRIVER10") (pin "8") (pinfunction "VCC2_8") (pintype "power_in"))
      (node (ref "DRIVER11") (pin "8") (pinfunction "VCC2_8") (pintype "power_in"))
      (node (ref "DRIVER12") (pin "8") (pinfunction "VCC2_8") (pintype "power_in"))
      (node (ref "DRIVER13") (pin "8") (pinfunction "VCC2_8") (pintype "power_in"))
      (node (ref "DRIVER2") (pin "8") (pinfunction "VCC2_8") (pintype "power_in"))
      (node (ref "DRIVER3") (pin "8") (pinfunction "VCC2_8") (pintype "power_in"))
      (node (ref "DRIVER4") (pin "8") (pinfunction "VCC2_8") (pintype "power_in"))
      (node (ref "DRIVER5") (pin "8") (pinfunction "VCC2_8") (pintype "power_in"))
      (node (ref "DRIVER6") (pin "8") (pinfunction "VCC2_8") (pintype "power_in"))
      (node (ref "DRIVER7") (pin "8") (pinfunction "VCC2_8") (pintype "power_in"))
      (node (ref "DRIVER8") (pin "8") (pinfunction "VCC2_8") (pintype "power_in"))
      (node (ref "DRIVER9") (pin "8") (pinfunction "VCC2_8") (pintype "power_in"))
      (node (ref "R1") (pin "P$2") (pinfunction "2_P$2") (pintype "passive"))
      (node (ref "VCCMOTOR") (pin "2") (pinfunction "2_2") (pintype "passive"))
    )
    (net (code "116") (name "unconnected-(DRIVER13-3Y-Pad11)") (class "Default")
      (node (ref "DRIVER13") (pin "11") (pinfunction "3Y_11") (pintype "output"))
    )
    (net (code "117") (name "unconnected-(DRIVER13-4Y-Pad14)") (class "Default")
      (node (ref "DRIVER13") (pin "14") (pinfunction "4Y_14") (pintype "output"))
    )
    (net (code "118") (name "unconnected-(SR7-QC-Pad2)") (class "Default")
      (node (ref "SR7") (pin "2") (pinfunction "QC_2") (pintype "tri_state"))
    )
    (net (code "119") (name "unconnected-(SR7-QD-Pad3)") (class "Default")
      (node (ref "SR7") (pin "3") (pinfunction "QD_3") (pintype "tri_state"))
    )
    (net (code "120") (name "unconnected-(SR7-QE-Pad4)") (class "Default")
      (node (ref "SR7") (pin "4") (pinfunction "QE_4") (pintype "tri_state"))
    )
    (net (code "121") (name "unconnected-(SR7-QF-Pad5)") (class "Default")
      (node (ref "SR7") (pin "5") (pinfunction "QF_5") (pintype "tri_state"))
    )
    (net (code "122") (name "unconnected-(SR7-QG-Pad6)") (class "Default")
      (node (ref "SR7") (pin "6") (pinfunction "QG_6") (pintype "tri_state"))
    )
    (net (code "123") (name "unconnected-(SR7-QH-Pad7)") (class "Default")
      (node (ref "SR7") (pin "7") (pinfunction "QH_7") (pintype "tri_state"))
    )
  )
)
